# Chessbot_v6.net
KiCad netlist of a schematic drawn in EAGLE
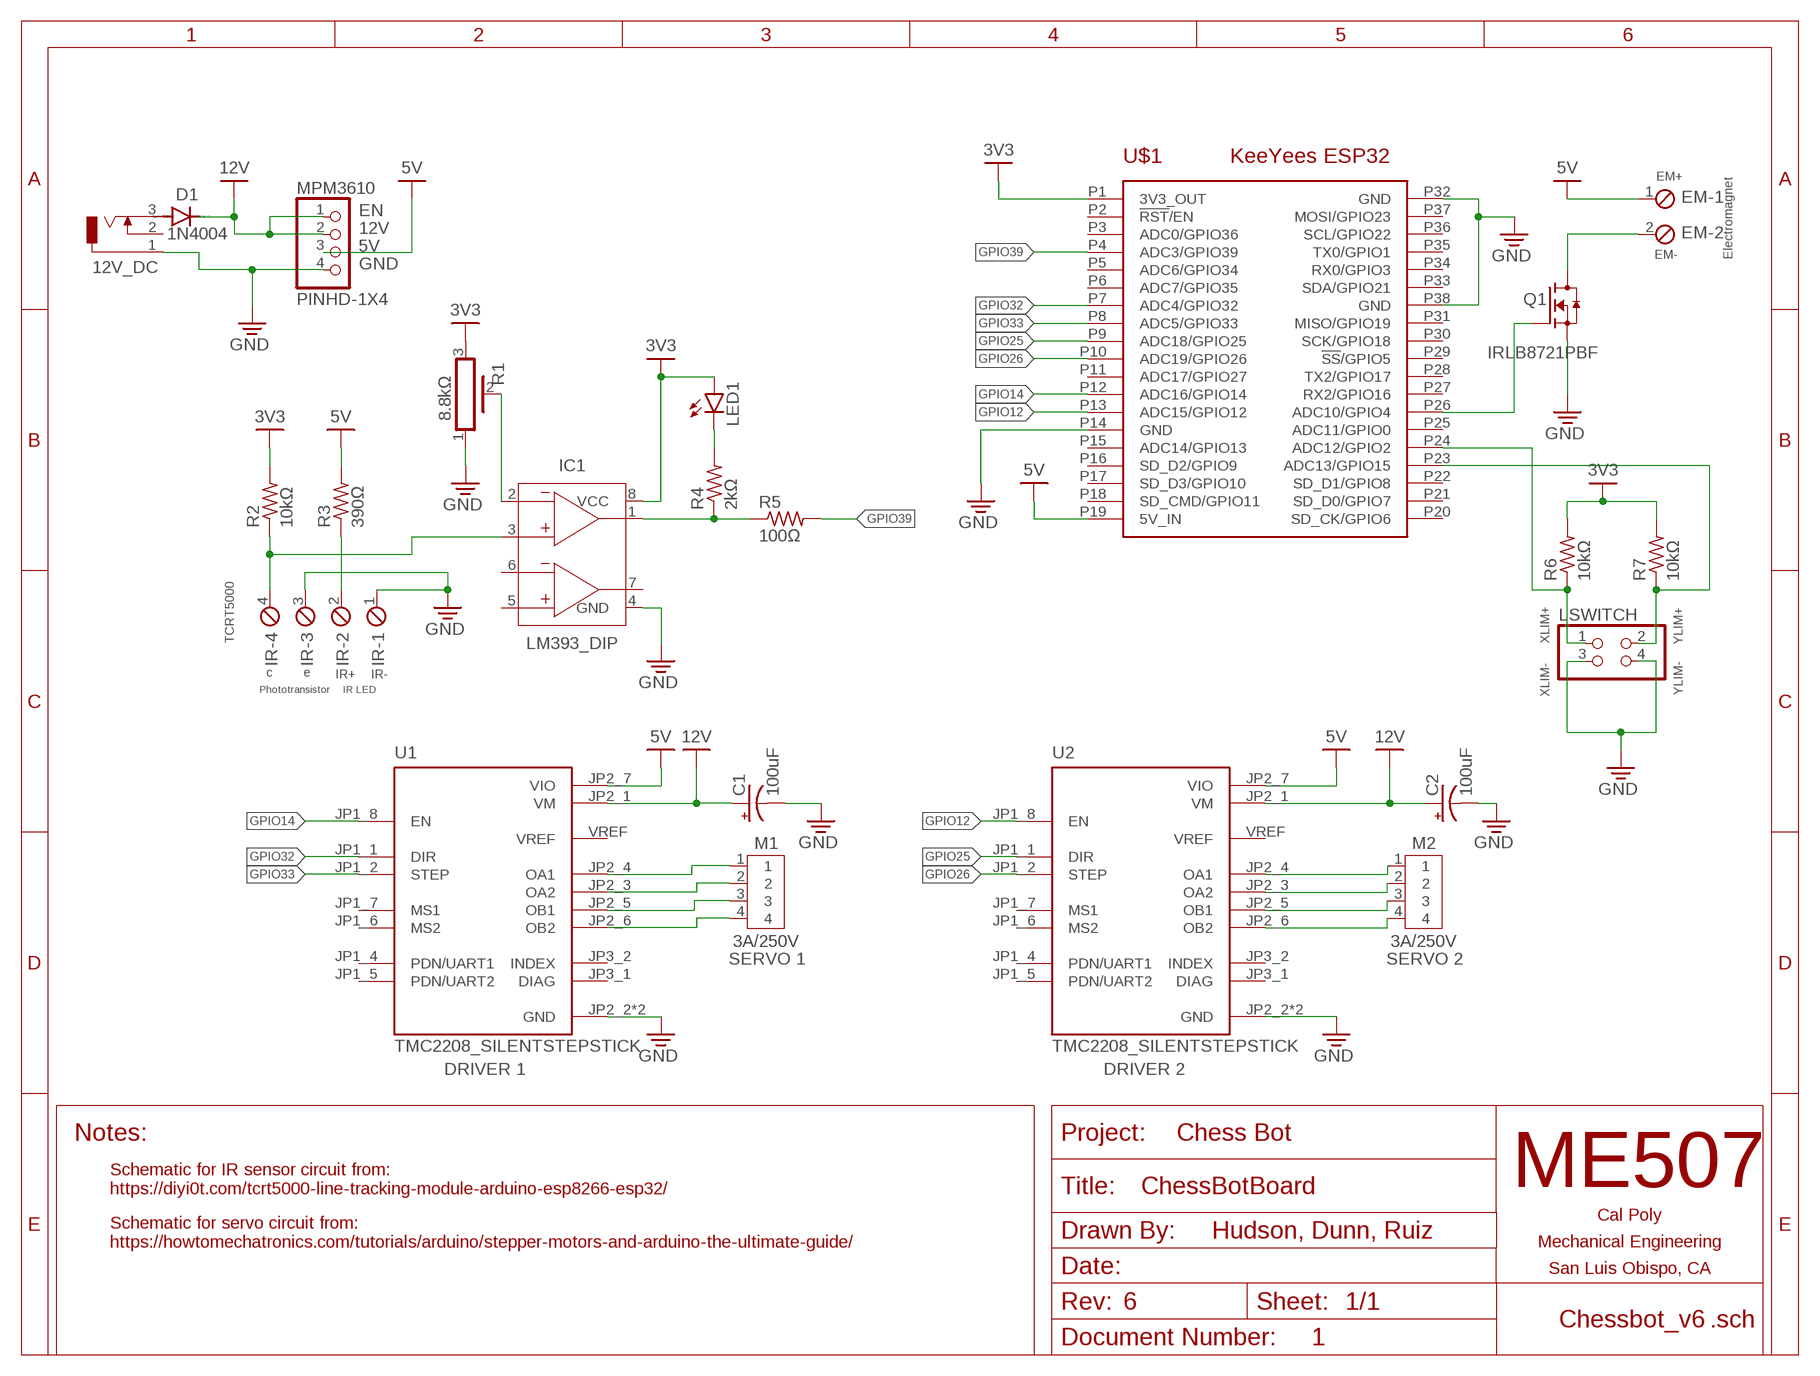
[diagram p0: schematic, sheet 1]

(export (version "E")
  (design (tool "Eeschema 10.0.6"))
  (components
    (comp (ref "12V_DC")
      (value "DCJ0303")
      (footprint "eagle-import:DCJ0303")
      (libsource (lib "eagle-import") (part "DCJ0303"))
    )
    (comp (ref "C1")
      (value "100uF")
      (footprint "eagle-import:E2,5-6")
      (libsource (lib "eagle-import") (part "CPOL-USE2.5-6"))
    )
    (comp (ref "C2")
      (value "100uF")
      (footprint "eagle-import:E2,5-6")
      (libsource (lib "eagle-import") (part "CPOL-USE2.5-6"))
    )
    (comp (ref "D1")
      (value "1N4004")
      (footprint "eagle-import:DO41-10")
      (libsource (lib "eagle-import") (part "1N4004"))
    )
    (comp (ref "EM")
      (value "SCREWTERM_2P_254")
      (footprint "eagle-import:2POL254")
      (libsource (lib "eagle-import") (part "SCREWTERM_2P_254"))
    )
    (comp (ref "IC1")
      (value "LM393_DIP")
      (footprint "eagle-import:DIP826W53P254L959H508Q8B")
      (fields (field (name "MANUFACTURER") "Generic"))
      (libsource (lib "eagle-import") (part "LM393_DIP"))
    )
    (comp (ref "IR")
      (value "SCREWTERM_4P_254")
      (footprint "eagle-import:4POL254")
      (libsource (lib "eagle-import") (part "SCREWTERM_4P_254"))
    )
    (comp (ref "LED1")
      (value "LEDSMT1206")
      (footprint "eagle-import:1206")
      (libsource (lib "eagle-import") (part "LEDSMT1206"))
    )
    (comp (ref "LSWITCH")
      (value "PINHD-2X2")
      (footprint "eagle-import:2X02")
      (libsource (lib "eagle-import") (part "PINHD-2X2"))
    )
    (comp (ref "M1")
      (value "3A/250V")
      (footprint "eagle-import:B4B-XH-A")
      (fields (field (name "MANUFACTURER") "JST (XH connector)") (field (name "MPN") "B4B-XH-A"))
      (libsource (lib "eagle-import") (part "B4B-XH-A"))
    )
    (comp (ref "M2")
      (value "3A/250V")
      (footprint "eagle-import:B4B-XH-A")
      (fields (field (name "MANUFACTURER") "JST (XH connector)") (field (name "MPN") "B4B-XH-A"))
      (libsource (lib "eagle-import") (part "B4B-XH-A"))
    )
    (comp (ref "MPM3610")
      (value "PINHD-1X4")
      (footprint "eagle-import:1X04")
      (libsource (lib "eagle-import") (part "PINHD-1X4"))
    )
    (comp (ref "Q1")
      (value "IRLB8721PBF")
      (footprint "eagle-import:TO254P1067X483X2057-3")
      (fields (field (name "MF") "Infineon Technologies"))
      (libsource (lib "eagle-import") (part "IRLB8721PBF"))
    )
    (comp (ref "R1")
      (value "8.8kΩ")
      (footprint "eagle-import:PV36Z")
      (fields (field (name "MANUFACTURER") "BOURNS") (field (name "MPN") "PV36Z"))
      (libsource (lib "eagle-import") (part "PV36Z"))
    )
    (comp (ref "R2")
      (value "10kΩ")
      (footprint "eagle-import:R0805")
      (libsource (lib "eagle-import") (part "R-US_R0805"))
    )
    (comp (ref "R3")
      (value "390Ω")
      (footprint "eagle-import:R0805")
      (libsource (lib "eagle-import") (part "R-US_R0805"))
    )
    (comp (ref "R4")
      (value "2kΩ")
      (footprint "eagle-import:R0805")
      (libsource (lib "eagle-import") (part "R-US_R0805"))
    )
    (comp (ref "R5")
      (value "100Ω")
      (footprint "eagle-import:R0805")
      (libsource (lib "eagle-import") (part "R-US_R0805"))
    )
    (comp (ref "R6")
      (value "10kΩ")
      (footprint "eagle-import:R0805")
      (libsource (lib "eagle-import") (part "R-US_R0805"))
    )
    (comp (ref "R7")
      (value "10kΩ")
      (footprint "eagle-import:R0805")
      (libsource (lib "eagle-import") (part "R-US_R0805"))
    )
    (comp (ref "U$1")
      (value "KEEYEES_ESP32EXT")
      (footprint "eagle-import:KEEYEES_ESP32_EXTENDED")
      (libsource (lib "eagle-import") (part "KEEYEES_ESP32EXT"))
    )
    (comp (ref "U1")
      (value "TMC2208_SILENTSTEPSTICK")
      (footprint "eagle-import:MODULE_TMC2208_SILENTSTEPSTICK")
      (fields (field (name "MF") "Trinamic Motion") (field (name "MP") "TMC2208 SILENTSTEPSTICK"))
      (libsource (lib "eagle-import") (part "TMC2208_SILENTSTEPSTICK"))
    )
    (comp (ref "U2")
      (value "TMC2208_SILENTSTEPSTICK")
      (footprint "eagle-import:MODULE_TMC2208_SILENTSTEPSTICK")
      (fields (field (name "MF") "Trinamic Motion") (field (name "MP") "TMC2208 SILENTSTEPSTICK"))
      (libsource (lib "eagle-import") (part "TMC2208_SILENTSTEPSTICK"))
    )
  )
  (nets
    (net (code "1") (name "3V3") (class "Default")
      (node (ref "IC1") (pin "8") (pinfunction "VCC_8") (pintype "bidirectional"))
      (node (ref "LED1") (pin "A") (pinfunction "A_A") (pintype "passive"))
      (node (ref "R1") (pin "3") (pinfunction "P$3_3") (pintype "passive"))
      (node (ref "R2") (pin "2") (pinfunction "2_2") (pintype "passive"))
      (node (ref "R6") (pin "2") (pinfunction "2_2") (pintype "passive"))
      (node (ref "R7") (pin "2") (pinfunction "2_2") (pintype "passive"))
      (node (ref "U$1") (pin "P1") (pinfunction "3V3_OUT_P1") (pintype "power_in"))
    )
    (net (code "2") (name "5V") (class "Default")
      (node (ref "EM") (pin "1") (pinfunction "1_1") (pintype "passive"))
      (node (ref "MPM3610") (pin "3") (pinfunction "3_3") (pintype "passive"))
      (node (ref "R3") (pin "2") (pinfunction "2_2") (pintype "passive"))
      (node (ref "U$1") (pin "P19") (pinfunction "5V_IN_P19") (pintype "power_in"))
      (node (ref "U1") (pin "JP2_7") (pinfunction "VIO_JP2_7") (pintype "power_in"))
      (node (ref "U2") (pin "JP2_7") (pinfunction "VIO_JP2_7") (pintype "power_in"))
    )
    (net (code "3") (name "12V") (class "Default")
      (node (ref "C1") (pin "+") (pinfunction "+_+") (pintype "passive"))
      (node (ref "C2") (pin "+") (pinfunction "+_+") (pintype "passive"))
      (node (ref "D1") (pin "C") (pinfunction "C_C") (pintype "passive"))
      (node (ref "MPM3610") (pin "1") (pinfunction "1_1") (pintype "passive"))
      (node (ref "MPM3610") (pin "2") (pinfunction "2_2") (pintype "passive"))
      (node (ref "U1") (pin "JP2_1") (pinfunction "VM_JP2_1") (pintype "power_in"))
      (node (ref "U2") (pin "JP2_1") (pinfunction "VM_JP2_1") (pintype "power_in"))
    )
    (net (code "4") (name "GND") (class "Default")
      (node (ref "12V_DC") (pin "1") (pinfunction "1_1") (pintype "passive"))
      (node (ref "C1") (pin "-") (pinfunction "-_-") (pintype "passive"))
      (node (ref "C2") (pin "-") (pinfunction "-_-") (pintype "passive"))
      (node (ref "IC1") (pin "4") (pinfunction "GND_4") (pintype "bidirectional"))
      (node (ref "IR") (pin "1") (pinfunction "1_1") (pintype "passive"))
      (node (ref "IR") (pin "3") (pinfunction "1_3") (pintype "passive"))
      (node (ref "LSWITCH") (pin "3") (pinfunction "3_3") (pintype "passive"))
      (node (ref "LSWITCH") (pin "4") (pinfunction "4_4") (pintype "passive"))
      (node (ref "MPM3610") (pin "4") (pinfunction "4_4") (pintype "passive"))
      (node (ref "Q1") (pin "3") (pinfunction "S_3") (pintype "passive"))
      (node (ref "R1") (pin "1") (pinfunction "P$1_1") (pintype "passive"))
      (node (ref "U$1") (pin "P14") (pinfunction "GND_P14") (pintype "power_in"))
      (node (ref "U$1") (pin "P32") (pinfunction "GND_P32") (pintype "power_in"))
      (node (ref "U$1") (pin "P38") (pinfunction "GND_P38") (pintype "power_in"))
      (node (ref "U1") (pin "JP2_2") (pinfunction "GND_JP2_2") (pintype "power_in"))
      (node (ref "U1") (pin "JP2_8") (pinfunction "GND_JP2_8") (pintype "power_in"))
      (node (ref "U2") (pin "JP2_2") (pinfunction "GND_JP2_2") (pintype "power_in"))
      (node (ref "U2") (pin "JP2_8") (pinfunction "GND_JP2_8") (pintype "power_in"))
    )
    (net (code "5") (name "GPIO12") (class "Default")
      (node (ref "U$1") (pin "P13") (pinfunction "ADC15/GPIO12_P13") (pintype "bidirectional"))
      (node (ref "U2") (pin "JP1_8") (pinfunction "EN_JP1_8") (pintype "input"))
    )
    (net (code "6") (name "GPIO14") (class "Default")
      (node (ref "U$1") (pin "P12") (pinfunction "ADC16/GPIO14_P12") (pintype "bidirectional"))
      (node (ref "U1") (pin "JP1_8") (pinfunction "EN_JP1_8") (pintype "input"))
    )
    (net (code "7") (name "GPIO25") (class "Default")
      (node (ref "U$1") (pin "P9") (pinfunction "ADC18/GPIO25_P9") (pintype "bidirectional"))
      (node (ref "U2") (pin "JP1_1") (pinfunction "DIR_JP1_1") (pintype "input"))
    )
    (net (code "8") (name "GPIO26") (class "Default")
      (node (ref "U$1") (pin "P10") (pinfunction "ADC19/GPIO26_P10") (pintype "bidirectional"))
      (node (ref "U2") (pin "JP1_2") (pinfunction "STEP_JP1_2") (pintype "input"))
    )
    (net (code "9") (name "GPIO32") (class "Default")
      (node (ref "U$1") (pin "P7") (pinfunction "ADC4/GPIO32_P7") (pintype "bidirectional"))
      (node (ref "U1") (pin "JP1_1") (pinfunction "DIR_JP1_1") (pintype "input"))
    )
    (net (code "10") (name "GPIO33") (class "Default")
      (node (ref "U$1") (pin "P8") (pinfunction "ADC5/GPIO33_P8") (pintype "bidirectional"))
      (node (ref "U1") (pin "JP1_2") (pinfunction "STEP_JP1_2") (pintype "input"))
    )
    (net (code "11") (name "GPIO39") (class "Default")
      (node (ref "R5") (pin "2") (pinfunction "2_2") (pintype "passive"))
      (node (ref "U$1") (pin "P4") (pinfunction "ADC3/GPIO39_P4") (pintype "bidirectional"))
    )
    (net (code "12") (name "Net-(12V_DC-Pad3)") (class "Default")
      (node (ref "12V_DC") (pin "3") (pinfunction "3_3") (pintype "passive"))
      (node (ref "D1") (pin "A") (pinfunction "A_A") (pintype "passive"))
    )
    (net (code "13") (name "Net-(EMB-1)") (class "Default")
      (node (ref "EM") (pin "2") (pinfunction "1_2") (pintype "passive"))
      (node (ref "Q1") (pin "2") (pinfunction "D_2") (pintype "passive"))
    )
    (net (code "14") (name "Net-(IC1-+IN1)") (class "Default")
      (node (ref "IC1") (pin "3") (pinfunction "+IN1_3") (pintype "input"))
      (node (ref "IR") (pin "4") (pinfunction "1_4") (pintype "passive"))
      (node (ref "R2") (pin "1") (pinfunction "1_1") (pintype "passive"))
    )
    (net (code "15") (name "Net-(IC1--IN1)") (class "Default")
      (node (ref "IC1") (pin "2") (pinfunction "-IN1_2") (pintype "input"))
      (node (ref "R1") (pin "2") (pinfunction "P$2_2") (pintype "passive"))
    )
    (net (code "16") (name "Net-(IC1-OUT1)") (class "Default")
      (node (ref "IC1") (pin "1") (pinfunction "OUT1_1") (pintype "output"))
      (node (ref "R4") (pin "1") (pinfunction "1_1") (pintype "passive"))
      (node (ref "R5") (pin "1") (pinfunction "1_1") (pintype "passive"))
    )
    (net (code "17") (name "Net-(IRB-1)") (class "Default")
      (node (ref "IR") (pin "2") (pinfunction "1_2") (pintype "passive"))
      (node (ref "R3") (pin "1") (pinfunction "1_1") (pintype "passive"))
    )
    (net (code "18") (name "Net-(LED1-PadC)") (class "Default")
      (node (ref "LED1") (pin "C") (pinfunction "C_C") (pintype "passive"))
      (node (ref "R4") (pin "2") (pinfunction "2_2") (pintype "passive"))
    )
    (net (code "19") (name "Net-(Q1-G)") (class "Default")
      (node (ref "Q1") (pin "1") (pinfunction "G_1") (pintype "passive"))
      (node (ref "U$1") (pin "P26") (pinfunction "ADC10/GPIO4_P26") (pintype "bidirectional"))
    )
    (net (code "20") (name "Net-(U$1-ADC12{slash}GPIO2)") (class "Default")
      (node (ref "LSWITCH") (pin "1") (pinfunction "1_1") (pintype "passive"))
      (node (ref "R6") (pin "1") (pinfunction "1_1") (pintype "passive"))
      (node (ref "U$1") (pin "P24") (pinfunction "ADC12/GPIO2_P24") (pintype "bidirectional"))
    )
    (net (code "21") (name "Net-(U$1-ADC13{slash}GPIO15)") (class "Default")
      (node (ref "LSWITCH") (pin "2") (pinfunction "2_2") (pintype "passive"))
      (node (ref "R7") (pin "1") (pinfunction "1_1") (pintype "passive"))
      (node (ref "U$1") (pin "P23") (pinfunction "ADC13/GPIO15_P23") (pintype "bidirectional"))
    )
    (net (code "22") (name "Net-(U1-OA1)") (class "Default")
      (node (ref "M1") (pin "1") (pinfunction "1_1") (pintype "bidirectional"))
      (node (ref "U1") (pin "JP2_4") (pinfunction "OA1_JP2_4") (pintype "passive"))
    )
    (net (code "23") (name "Net-(U1-OA2)") (class "Default")
      (node (ref "M1") (pin "2") (pinfunction "2_2") (pintype "bidirectional"))
      (node (ref "U1") (pin "JP2_3") (pinfunction "OA2_JP2_3") (pintype "passive"))
    )
    (net (code "24") (name "Net-(U1-OB1)") (class "Default")
      (node (ref "M1") (pin "3") (pinfunction "3_3") (pintype "bidirectional"))
      (node (ref "U1") (pin "JP2_5") (pinfunction "OB1_JP2_5") (pintype "passive"))
    )
    (net (code "25") (name "Net-(U1-OB2)") (class "Default")
      (node (ref "M1") (pin "4") (pinfunction "4_4") (pintype "bidirectional"))
      (node (ref "U1") (pin "JP2_6") (pinfunction "OB2_JP2_6") (pintype "passive"))
    )
    (net (code "26") (name "Net-(U2-OA1)") (class "Default")
      (node (ref "M2") (pin "1") (pinfunction "1_1") (pintype "bidirectional"))
      (node (ref "U2") (pin "JP2_4") (pinfunction "OA1_JP2_4") (pintype "passive"))
    )
    (net (code "27") (name "Net-(U2-OA2)") (class "Default")
      (node (ref "M2") (pin "2") (pinfunction "2_2") (pintype "bidirectional"))
      (node (ref "U2") (pin "JP2_3") (pinfunction "OA2_JP2_3") (pintype "passive"))
    )
    (net (code "28") (name "Net-(U2-OB1)") (class "Default")
      (node (ref "M2") (pin "3") (pinfunction "3_3") (pintype "bidirectional"))
      (node (ref "U2") (pin "JP2_5") (pinfunction "OB1_JP2_5") (pintype "passive"))
    )
    (net (code "29") (name "Net-(U2-OB2)") (class "Default")
      (node (ref "M2") (pin "4") (pinfunction "4_4") (pintype "bidirectional"))
      (node (ref "U2") (pin "JP2_6") (pinfunction "OB2_JP2_6") (pintype "passive"))
    )
    (net (code "30") (name "unconnected-(12V_DC-Pad2)") (class "Default")
      (node (ref "12V_DC") (pin "2") (pinfunction "2_2") (pintype "passive"))
    )
    (net (code "31") (name "unconnected-(IC1-+IN2-Pad5)") (class "Default")
      (node (ref "IC1") (pin "5") (pinfunction "+IN2_5") (pintype "input"))
    )
    (net (code "32") (name "unconnected-(IC1--IN2-Pad6)") (class "Default")
      (node (ref "IC1") (pin "6") (pinfunction "-IN2_6") (pintype "input"))
    )
    (net (code "33") (name "unconnected-(IC1-OUT2-Pad7)") (class "Default")
      (node (ref "IC1") (pin "7") (pinfunction "OUT2_7") (pintype "output"))
    )
    (net (code "34") (name "unconnected-(U$1-ADC0{slash}GPIO36-PadP3)") (class "Default")
      (node (ref "U$1") (pin "P3") (pinfunction "ADC0/GPIO36_P3") (pintype "bidirectional"))
    )
    (net (code "35") (name "unconnected-(U$1-ADC6{slash}GPIO34-PadP5)") (class "Default")
      (node (ref "U$1") (pin "P5") (pinfunction "ADC6/GPIO34_P5") (pintype "bidirectional"))
    )
    (net (code "36") (name "unconnected-(U$1-ADC7{slash}GPIO35-PadP6)") (class "Default")
      (node (ref "U$1") (pin "P6") (pinfunction "ADC7/GPIO35_P6") (pintype "bidirectional"))
    )
    (net (code "37") (name "unconnected-(U$1-ADC11{slash}GPIO0-PadP25)") (class "Default")
      (node (ref "U$1") (pin "P25") (pinfunction "ADC11/GPIO0_P25") (pintype "bidirectional"))
    )
    (net (code "38") (name "unconnected-(U$1-ADC14{slash}GPIO13-PadP15)") (class "Default")
      (node (ref "U$1") (pin "P15") (pinfunction "ADC14/GPIO13_P15") (pintype "bidirectional"))
    )
    (net (code "39") (name "unconnected-(U$1-ADC17{slash}GPIO27-PadP11)") (class "Default")
      (node (ref "U$1") (pin "P11") (pinfunction "ADC17/GPIO27_P11") (pintype "bidirectional"))
    )
    (net (code "40") (name "unconnected-(U$1-MISO{slash}GPIO19-PadP31)") (class "Default")
      (node (ref "U$1") (pin "P31") (pinfunction "MISO/GPIO19_P31") (pintype "bidirectional"))
    )
    (net (code "41") (name "unconnected-(U$1-MOSI{slash}GPIO23-PadP37)") (class "Default")
      (node (ref "U$1") (pin "P37") (pinfunction "MOSI/GPIO23_P37") (pintype "bidirectional"))
    )
    (net (code "42") (name "unconnected-(U$1-RX0{slash}GPIO3-PadP34)") (class "Default")
      (node (ref "U$1") (pin "P34") (pinfunction "RX0/GPIO3_P34") (pintype "bidirectional"))
    )
    (net (code "43") (name "unconnected-(U$1-RX2{slash}GPIO16-PadP27)") (class "Default")
      (node (ref "U$1") (pin "P27") (pinfunction "RX2/GPIO16_P27") (pintype "bidirectional"))
    )
    (net (code "44") (name "unconnected-(U$1-SCK{slash}GPIO18-PadP30)") (class "Default")
      (node (ref "U$1") (pin "P30") (pinfunction "SCK/GPIO18_P30") (pintype "bidirectional"))
    )
    (net (code "45") (name "unconnected-(U$1-SCL{slash}GPIO22-PadP36)") (class "Default")
      (node (ref "U$1") (pin "P36") (pinfunction "SCL/GPIO22_P36") (pintype "bidirectional"))
    )
    (net (code "46") (name "unconnected-(U$1-SDA{slash}GPIO21-PadP33)") (class "Default")
      (node (ref "U$1") (pin "P33") (pinfunction "SDA/GPIO21_P33") (pintype "bidirectional"))
    )
    (net (code "47") (name "unconnected-(U$1-SD_CK{slash}GPIO6-PadP20)") (class "Default")
      (node (ref "U$1") (pin "P20") (pinfunction "SD_CK/GPIO6_P20") (pintype "bidirectional"))
    )
    (net (code "48") (name "unconnected-(U$1-SD_CMD{slash}GPIO11-PadP18)") (class "Default")
      (node (ref "U$1") (pin "P18") (pinfunction "SD_CMD/GPIO11_P18") (pintype "bidirectional"))
    )
    (net (code "49") (name "unconnected-(U$1-SD_D0{slash}GPIO7-PadP21)") (class "Default")
      (node (ref "U$1") (pin "P21") (pinfunction "SD_D0/GPIO7_P21") (pintype "bidirectional"))
    )
    (net (code "50") (name "unconnected-(U$1-SD_D1{slash}GPIO8-PadP22)") (class "Default")
      (node (ref "U$1") (pin "P22") (pinfunction "SD_D1/GPIO8_P22") (pintype "bidirectional"))
    )
    (net (code "51") (name "unconnected-(U$1-SD_D2{slash}GPIO9-PadP16)") (class "Default")
      (node (ref "U$1") (pin "P16") (pinfunction "SD_D2/GPIO9_P16") (pintype "bidirectional"))
    )
    (net (code "52") (name "unconnected-(U$1-SD_D3{slash}GPIO10-PadP17)") (class "Default")
      (node (ref "U$1") (pin "P17") (pinfunction "SD_D3/GPIO10_P17") (pintype "bidirectional"))
    )
    (net (code "53") (name "unconnected-(U$1-TX0{slash}GPIO1-PadP35)") (class "Default")
      (node (ref "U$1") (pin "P35") (pinfunction "TX0/GPIO1_P35") (pintype "bidirectional"))
    )
    (net (code "54") (name "unconnected-(U$1-TX2{slash}GPIO17-PadP28)") (class "Default")
      (node (ref "U$1") (pin "P28") (pinfunction "TX2/GPIO17_P28") (pintype "bidirectional"))
    )
    (net (code "55") (name "unconnected-(U$1-~{RST}{slash}EN-PadP2)") (class "Default")
      (node (ref "U$1") (pin "P2") (pinfunction "~{RST}/EN_P2") (pintype "input"))
    )
    (net (code "56") (name "unconnected-(U$1-~{SS}{slash}GPIO5-PadP29)") (class "Default")
      (node (ref "U$1") (pin "P29") (pinfunction "~{SS}/GPIO5_P29") (pintype "bidirectional"))
    )
    (net (code "57") (name "unconnected-(U1-DIAG-PadJP3_1)") (class "Default")
      (node (ref "U1") (pin "JP3_1") (pinfunction "DIAG_JP3_1") (pintype "output"))
    )
    (net (code "58") (name "unconnected-(U1-INDEX-PadJP3_2)") (class "Default")
      (node (ref "U1") (pin "JP3_2") (pinfunction "INDEX_JP3_2") (pintype "output"))
    )
    (net (code "59") (name "unconnected-(U1-MS1-PadJP1_7)") (class "Default")
      (node (ref "U1") (pin "JP1_7") (pinfunction "MS1_JP1_7") (pintype "input"))
    )
    (net (code "60") (name "unconnected-(U1-MS2-PadJP1_6)") (class "Default")
      (node (ref "U1") (pin "JP1_6") (pinfunction "MS2_JP1_6") (pintype "input"))
    )
    (net (code "61") (name "unconnected-(U1-PDN{slash}UART1-PadJP1_4)") (class "Default")
      (node (ref "U1") (pin "JP1_4") (pinfunction "PDN/UART1_JP1_4") (pintype "bidirectional"))
    )
    (net (code "62") (name "unconnected-(U1-PDN{slash}UART2-PadJP1_5)") (class "Default")
      (node (ref "U1") (pin "JP1_5") (pinfunction "PDN/UART2_JP1_5") (pintype "bidirectional"))
    )
    (net (code "63") (name "unconnected-(U1-PadVREF)") (class "Default")
      (node (ref "U1") (pin "VREF") (pinfunction "VREF_VREF") (pintype "passive"))
    )
    (net (code "64") (name "unconnected-(U2-DIAG-PadJP3_1)") (class "Default")
      (node (ref "U2") (pin "JP3_1") (pinfunction "DIAG_JP3_1") (pintype "output"))
    )
    (net (code "65") (name "unconnected-(U2-INDEX-PadJP3_2)") (class "Default")
      (node (ref "U2") (pin "JP3_2") (pinfunction "INDEX_JP3_2") (pintype "output"))
    )
    (net (code "66") (name "unconnected-(U2-MS1-PadJP1_7)") (class "Default")
      (node (ref "U2") (pin "JP1_7") (pinfunction "MS1_JP1_7") (pintype "input"))
    )
    (net (code "67") (name "unconnected-(U2-MS2-PadJP1_6)") (class "Default")
      (node (ref "U2") (pin "JP1_6") (pinfunction "MS2_JP1_6") (pintype "input"))
    )
    (net (code "68") (name "unconnected-(U2-PDN{slash}UART1-PadJP1_4)") (class "Default")
      (node (ref "U2") (pin "JP1_4") (pinfunction "PDN/UART1_JP1_4") (pintype "bidirectional"))
    )
    (net (code "69") (name "unconnected-(U2-PDN{slash}UART2-PadJP1_5)") (class "Default")
      (node (ref "U2") (pin "JP1_5") (pinfunction "PDN/UART2_JP1_5") (pintype "bidirectional"))
    )
    (net (code "70") (name "unconnected-(U2-PadVREF)") (class "Default")
      (node (ref "U2") (pin "VREF") (pinfunction "VREF_VREF") (pintype "passive"))
    )
  )
)
